# estop_receiver_rev1.net
KiCad netlist of a schematic drawn in EasyEDA Pro
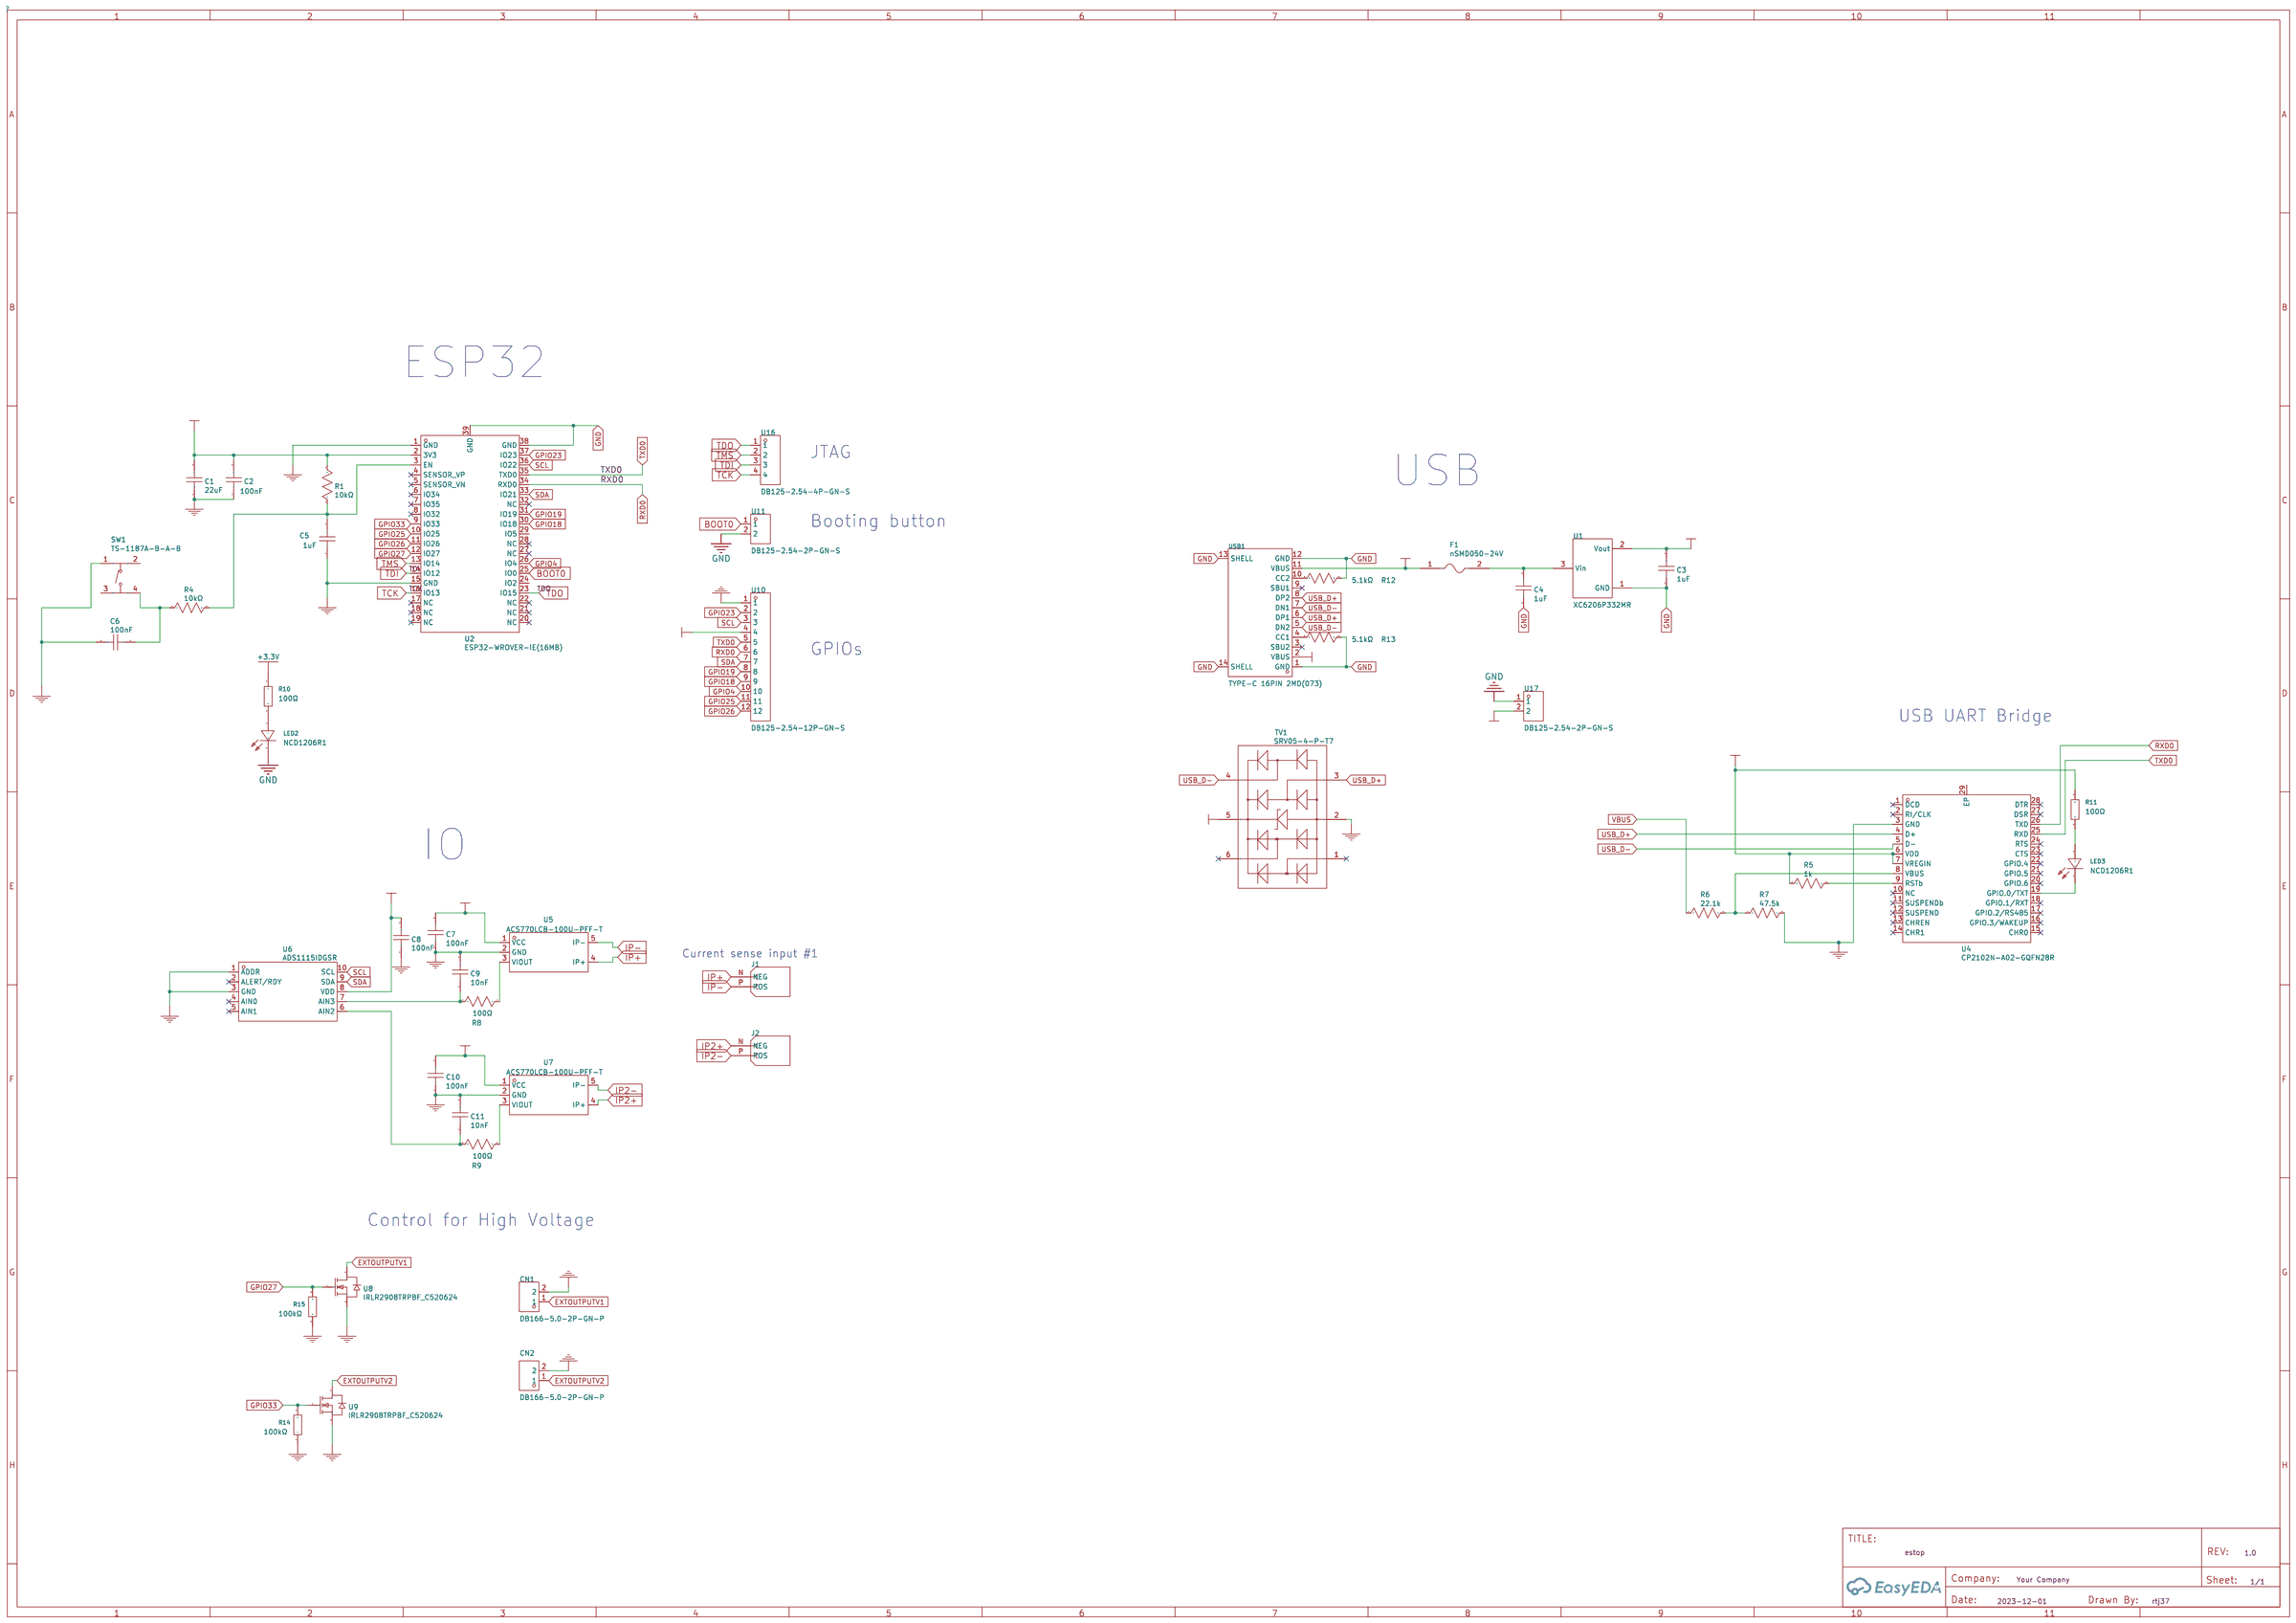
[diagram p0: schematic sheet]

(export (version "E")
  (design (tool "Eeschema 10.0.6"))
  (components
    (comp (ref "C1")
      (value "22uF")
      (fields
        (field (name "Manufacturer Part") "CL31A226KAHNNNE")
        (field (name "Manufacturer") "SAMSUNG(三星)")
      )
      (libsource (lib "easyedapro") (part "22u"))
    )
    (comp (ref "C2")
      (value "100nF")
      (fields (field (name "Manufacturer Part") "1206B104K500NT") (field (name "Manufacturer") "FH(风华)"))
      (libsource (lib "easyedapro") (part "0.1u"))
    )
    (comp (ref "C3")
      (value "1uF")
      (fields (field (name "Manufacturer Part") "1206B105K500NT") (field (name "Manufacturer") "FH(风华)"))
      (libsource (lib "easyedapro") (part "1u"))
    )
    (comp (ref "C4")
      (value "1uF")
      (fields (field (name "Manufacturer Part") "1206B105K500NT") (field (name "Manufacturer") "FH(风华)"))
      (libsource (lib "easyedapro") (part "1u"))
    )
    (comp (ref "C5")
      (value "1uF")
      (fields (field (name "Manufacturer Part") "1206B105K500NT") (field (name "Manufacturer") "FH(风华)"))
      (libsource (lib "easyedapro") (part "1u"))
    )
    (comp (ref "C6")
      (value "100nF")
      (fields (field (name "Manufacturer Part") "1206B104K500NT") (field (name "Manufacturer") "FH(风华)"))
      (libsource (lib "easyedapro") (part "0.1u"))
    )
    (comp (ref "C7")
      (value "100nF")
      (fields (field (name "Manufacturer Part") "1206B104K500NT") (field (name "Manufacturer") "FH(风华)"))
      (libsource (lib "easyedapro") (part "0.1u"))
    )
    (comp (ref "C8")
      (value "100nF")
      (fields (field (name "Manufacturer Part") "1206B104K500NT") (field (name "Manufacturer") "FH(风华)"))
      (libsource (lib "easyedapro") (part "100n"))
    )
    (comp (ref "C9")
      (value "10nF")
      (fields (field (name "Manufacturer Part") "1206B103K102CT") (field (name "Manufacturer") "Walsin(华新科)"))
      (libsource (lib "easyedapro") (part "10n"))
    )
    (comp (ref "C10")
      (value "100nF")
      (fields (field (name "Manufacturer Part") "1206B104K500NT") (field (name "Manufacturer") "FH(风华)"))
      (libsource (lib "easyedapro") (part "0.1u"))
    )
    (comp (ref "C11")
      (value "10nF")
      (fields (field (name "Manufacturer Part") "1206B103K102CT") (field (name "Manufacturer") "Walsin(华新科)"))
      (libsource (lib "easyedapro") (part "10n"))
    )
    (comp (ref "CN1")
      (value "DB166-5.0-2P-GN-P")
      (footprint "easyedapro:CONN-TH_2P-P5.00_DB166-5.0-2P-GN-P")
      (description "Pitch:5mm Number of Pins:2P")
      (fields (field (name "Manufacturer") "DORABO(地博电气)"))
      (libsource (lib "easyedapro") (part "DB166-5.0-2P-GN-P"))
    )
    (comp (ref "CN2")
      (value "DB166-5.0-2P-GN-P")
      (footprint "easyedapro:CONN-TH_2P-P5.00_DB166-5.0-2P-GN-P")
      (description "Pitch:5mm Number of Pins:2P")
      (fields (field (name "Manufacturer") "DORABO(地博电气)"))
      (libsource (lib "easyedapro") (part "DB166-5.0-2P-GN-P"))
    )
    (comp (ref "F1")
      (value "nSMD050-24V")
      (footprint "easyedapro:F1206")
      (fields (field (name "Manufacturer") "台湾陆海"))
      (libsource (lib "easyedapro") (part "nSMD050-24V"))
    )
    (comp (ref "J1")
      (value "XT90PW-F")
      (footprint "easyedapro:AMASS_XT90PW-F")
      (description "\\nSocket, DC supply, XT90, female, PIN:2, on PCBs, THT\\n")
      (libsource (lib "easyedapro") (part "XT90PW-F"))
    )
    (comp (ref "J2")
      (value "XT90PW-F")
      (footprint "easyedapro:AMASS_XT90PW-F")
      (description "\\nSocket, DC supply, XT90, female, PIN:2, on PCBs, THT\\n")
      (libsource (lib "easyedapro") (part "XT90PW-F"))
    )
    (comp (ref "LED2")
      (value "NCD1206R1")
      (footprint "easyedapro:LED1206-R-RD_RED")
      (fields (field (name "Manufacturer") "国星光电"))
      (libsource (lib "easyedapro") (part "FC-3215HRK-620D"))
    )
    (comp (ref "LED3")
      (value "NCD1206R1")
      (footprint "easyedapro:LED1206-R-RD_RED")
      (fields (field (name "Manufacturer") "国星光电"))
      (libsource (lib "easyedapro") (part "FC-3215HRK-620D"))
    )
    (comp (ref "R1")
      (value "10kΩ")
      (fields
        (field (name "Manufacturer Part") "1206W4F1002T5E")
        (field (name "Manufacturer") "UNI-ROYAL(厚声)")
      )
      (libsource (lib "easyedapro") (part "10k"))
    )
    (comp (ref "R4")
      (value "10kΩ")
      (fields
        (field (name "Manufacturer Part") "1206W4F1002T5E")
        (field (name "Manufacturer") "UNI-ROYAL(厚声)")
      )
      (libsource (lib "easyedapro") (part "0"))
    )
    (comp (ref "R5") (value "1k") (footprint "easyedapro:R1206") (libsource (lib "easyedapro") (part "1k")))
    (comp (ref "R6")
      (value "22.1k")
      (footprint "easyedapro:R1206")
      (libsource (lib "easyedapro") (part "22.1k"))
    )
    (comp (ref "R7")
      (value "47.5k")
      (footprint "easyedapro:R1206")
      (libsource (lib "easyedapro") (part "47.5k"))
    )
    (comp (ref "R8")
      (value "100Ω")
      (fields
        (field (name "Manufacturer Part") "1206W4F1000T5E")
        (field (name "Manufacturer") "UNI-ROYAL(厚声)")
      )
      (libsource (lib "easyedapro") (part "100"))
    )
    (comp (ref "R9")
      (value "100Ω")
      (fields
        (field (name "Manufacturer Part") "1206W4F1000T5E")
        (field (name "Manufacturer") "UNI-ROYAL(厚声)")
      )
      (libsource (lib "easyedapro") (part "100"))
    )
    (comp (ref "R10")
      (value "100Ω")
      (footprint "easyedapro:R1206")
      (fields
        (field (name "Manufacturer Part") "1206W4F1000T5E")
        (field (name "Manufacturer") "UNI-ROYAL(厚声)")
      )
      (libsource (lib "easyedapro") (part "1206W4F1000T5E"))
    )
    (comp (ref "R11")
      (value "100Ω")
      (footprint "easyedapro:R1206")
      (fields
        (field (name "Manufacturer Part") "1206W4F1000T5E")
        (field (name "Manufacturer") "UNI-ROYAL(厚声)")
      )
      (libsource (lib "easyedapro") (part "1206W4F1000T5E"))
    )
    (comp (ref "R12")
      (value "5.1kΩ")
      (fields
        (field (name "Manufacturer Part") "1206W4F5101T5E")
        (field (name "Manufacturer") "UNI-ROYAL(厚声)")
      )
      (libsource (lib "easyedapro") (part "5.1k"))
    )
    (comp (ref "R13")
      (value "5.1kΩ")
      (fields
        (field (name "Manufacturer Part") "1206W4F5101T5E")
        (field (name "Manufacturer") "UNI-ROYAL(厚声)")
      )
      (libsource (lib "easyedapro") (part "5.1k"))
    )
    (comp (ref "R14")
      (value "100kΩ")
      (footprint "easyedapro:R1206")
      (fields
        (field (name "Manufacturer Part") "1206W4F1003T5E")
        (field (name "Manufacturer") "UNI-ROYAL(厚声)")
      )
      (libsource (lib "easyedapro") (part "1206W4F1003T5E"))
    )
    (comp (ref "R15")
      (value "100kΩ")
      (footprint "easyedapro:R1206")
      (fields
        (field (name "Manufacturer Part") "1206W4F1003T5E")
        (field (name "Manufacturer") "UNI-ROYAL(厚声)")
      )
      (libsource (lib "easyedapro") (part "1206W4F1003T5E"))
    )
    (comp (ref "SW1")
      (value "TS-1187A-B-A-B")
      (footprint "easyedapro:SW-SMD_4P-L5.1-W5.1-P3.70-LS6.5-TL-2")
      (fields (field (name "Manufacturer") "XKB Connectivity(中国星坤)"))
      (libsource (lib "easyedapro") (part "TS-1187A-B-A-B"))
    )
    (comp (ref "TV1")
      (value "SRV05-4-P-T7")
      (footprint "easyedapro:SOT-23-6_L2.9-W1.6-P0.95-LS2.8-BR")
      (fields (field (name "Manufacturer") "PROTEK"))
      (libsource (lib "easyedapro") (part "SRV05-4-P-T7"))
    )
    (comp (ref "U1")
      (value "XC6206P332MR")
      (footprint "easyedapro:SOT-23-3_L2.9-W1.6-P1.90-LS2.8-BR")
      (fields (field (name "Manufacturer") "TOREX(特瑞仕)"))
      (libsource (lib "easyedapro") (part "XC6206P332MR"))
    )
    (comp (ref "U2")
      (value "ESP32-WROVER-IE(16MB)")
      (footprint "easyedapro:WIFI-SMD_ESP32-WROVER-E")
      (fields
        (field (name "Manufacturer Part") "ESP32-WROVER-IE-N16R8")
        (field (name "Manufacturer") "ESPRESSIF(乐鑫)")
      )
      (libsource (lib "easyedapro") (part "ESP32-WROVER-IE(16MB)"))
    )
    (comp (ref "U4")
      (value "CP2102N-A02-GQFN28R")
      (footprint "easyedapro:QFN-28_L5.0-W5.0-P0.50-TL-EP3.3")
      (fields (field (name "Manufacturer") "SILICON LABS(芯科)"))
      (libsource (lib "easyedapro") (part "CP2102N-A02-GQFN28R"))
    )
    (comp (ref "U5")
      (value "ACS770LCB-100U-PFF-T")
      (footprint "easyedapro:SENSOR-TH_ACS770LCB-100U-PFF-T")
      (fields (field (name "Manufacturer") "ALLEGRO(美国埃戈罗)"))
      (libsource (lib "easyedapro") (part "ACS770LCB-100U-PFF-T"))
    )
    (comp (ref "U6")
      (value "ADS1115IDGSR")
      (footprint "easyedapro:MSOP-10_L3.0-W3.0-P0.50-LS5.0-BL")
      (fields (field (name "Manufacturer") "TI(德州仪器)"))
      (libsource (lib "easyedapro") (part "ADS1115IDGSR"))
    )
    (comp (ref "U7")
      (value "ACS770LCB-100U-PFF-T")
      (footprint "easyedapro:SENSOR-TH_ACS770LCB-100U-PFF-T")
      (fields (field (name "Manufacturer") "ALLEGRO(美国埃戈罗)"))
      (libsource (lib "easyedapro") (part "ACS770LCB-100U-PFF-T"))
    )
    (comp (ref "U8")
      (value "IRLR2908TRPBF_C520624")
      (footprint "easyedapro:TO-252-3_L6.5-W6.1-P4.58-LS9.9-BR")
      (fields
        (field (name "Manufacturer Part") "IRLR2908TRPBF")
        (field (name "Manufacturer") "Infineon(英飞凌)")
      )
      (libsource (lib "easyedapro") (part "IRLR2908TRPBF_C520624"))
    )
    (comp (ref "U9")
      (value "IRLR2908TRPBF_C520624")
      (footprint "easyedapro:TO-252-3_L6.5-W6.1-P4.58-LS9.9-BR")
      (fields
        (field (name "Manufacturer Part") "IRLR2908TRPBF")
        (field (name "Manufacturer") "Infineon(英飞凌)")
      )
      (libsource (lib "easyedapro") (part "IRLR2908TRPBF_C520624"))
    )
    (comp (ref "U10")
      (value "DB125-2.54-12P-GN-S")
      (footprint "easyedapro:CONN-TH_DB125-2.54-12P-GN")
      (fields (field (name "Manufacturer") "DORABO(地博电气)"))
      (libsource (lib "easyedapro") (part "DB125-2.54-12P-GN"))
    )
    (comp (ref "U11")
      (value "DB125-2.54-2P-GN-S")
      (footprint "easyedapro:CONN-TH_DB125-2.54-2P-GN")
      (fields (field (name "Manufacturer") "DORABO(地博电气)"))
      (libsource (lib "easyedapro") (part "DB125-2.54-2P-GN"))
    )
    (comp (ref "U16")
      (value "DB125-2.54-4P-GN-S")
      (footprint "easyedapro:CONN-TH_DB125-2.54-4P-GN")
      (fields (field (name "Manufacturer") "DORABO(地博电气)"))
      (libsource (lib "easyedapro") (part "DB125-2.54-4P-GN"))
    )
    (comp (ref "U17")
      (value "DB125-2.54-2P-GN-S")
      (footprint "easyedapro:CONN-TH_DB125-2.54-2P-GN")
      (fields (field (name "Manufacturer") "DORABO(地博电气)"))
      (libsource (lib "easyedapro") (part "DB125-2.54-2P-GN"))
    )
    (comp (ref "USB1")
      (value "TYPE-C 16PIN 2MD(073)")
      (footprint "easyedapro:USB-C-SMD_TYPE-C-6PIN-2MD-073")
      (fields (field (name "Manufacturer") "SHOU HAN(首韩)"))
      (libsource (lib "easyedapro") (part "TYPE-C 16PIN 2MD(073)"))
    )
  )
  (nets
    (net (code "1") (name "+3.3V") (class "Default")
      (node (ref "C1") (pin "2") (pinfunction "2_2") (pintype "unspecified"))
      (node (ref "C2") (pin "2") (pinfunction "2_2") (pintype "unspecified"))
      (node (ref "C3") (pin "2") (pinfunction "2_2") (pintype "unspecified"))
      (node (ref "C8") (pin "2") (pinfunction "2_2") (pintype "unspecified"))
      (node (ref "R1") (pin "2") (pinfunction "2_2") (pintype "unspecified"))
      (node (ref "R10") (pin "1") (pinfunction "1_1") (pintype "input"))
      (node (ref "R11") (pin "1") (pinfunction "1_1") (pintype "input"))
      (node (ref "R5") (pin "1") (pinfunction "1_1") (pintype "unspecified"))
      (node (ref "U1") (pin "2") (pinfunction "Vout_2") (pintype "unspecified"))
      (node (ref "U10") (pin "4") (pinfunction "4_4") (pintype "unspecified"))
      (node (ref "U2") (pin "2") (pinfunction "3V3_2") (pintype "unspecified"))
      (node (ref "U4") (pin "6") (pinfunction "VDD_6") (pintype "unspecified"))
      (node (ref "U4") (pin "7") (pinfunction "VREGIN_7") (pintype "unspecified"))
      (node (ref "U6") (pin "8") (pinfunction "VDD_8") (pintype "unspecified"))
    )
    (net (code "2") (name "BOOT0") (class "Default")
      (node (ref "U11") (pin "1") (pinfunction "1_1") (pintype "unspecified"))
      (node (ref "U2") (pin "25") (pinfunction "IO0_25") (pintype "unspecified"))
    )
    (net (code "3") (name "EXTOUTPUTV1") (class "Default")
      (node (ref "CN1") (pin "1") (pinfunction "1_1") (pintype "unspecified"))
      (node (ref "U8") (pin "2") (pinfunction "D_2") (pintype "unspecified"))
    )
    (net (code "4") (name "EXTOUTPUTV2") (class "Default")
      (node (ref "CN2") (pin "1") (pinfunction "1_1") (pintype "unspecified"))
      (node (ref "U9") (pin "2") (pinfunction "D_2") (pintype "unspecified"))
    )
    (net (code "5") (name "GND") (class "Default")
      (node (ref "C1") (pin "1") (pinfunction "1_1") (pintype "unspecified"))
      (node (ref "C10") (pin "1") (pinfunction "1_1") (pintype "unspecified"))
      (node (ref "C11") (pin "2") (pinfunction "2_2") (pintype "unspecified"))
      (node (ref "C2") (pin "1") (pinfunction "1_1") (pintype "unspecified"))
      (node (ref "C3") (pin "1") (pinfunction "1_1") (pintype "unspecified"))
      (node (ref "C4") (pin "1") (pinfunction "1_1") (pintype "unspecified"))
      (node (ref "C5") (pin "1") (pinfunction "1_1") (pintype "unspecified"))
      (node (ref "C6") (pin "1") (pinfunction "1_1") (pintype "unspecified"))
      (node (ref "C7") (pin "1") (pinfunction "1_1") (pintype "unspecified"))
      (node (ref "C8") (pin "1") (pinfunction "1_1") (pintype "unspecified"))
      (node (ref "C9") (pin "2") (pinfunction "2_2") (pintype "unspecified"))
      (node (ref "CN1") (pin "2") (pinfunction "2_2") (pintype "unspecified"))
      (node (ref "CN2") (pin "2") (pinfunction "2_2") (pintype "unspecified"))
      (node (ref "LED2") (pin "2") (pinfunction "K_2") (pintype "input"))
      (node (ref "R12") (pin "2") (pinfunction "2_2") (pintype "unspecified"))
      (node (ref "R13") (pin "2") (pinfunction "2_2") (pintype "unspecified"))
      (node (ref "R14") (pin "1") (pinfunction "1_1") (pintype "input"))
      (node (ref "R15") (pin "1") (pinfunction "1_1") (pintype "input"))
      (node (ref "R7") (pin "2") (pinfunction "2_2") (pintype "unspecified"))
      (node (ref "SW1") (pin "1") (pinfunction "A_1") (pintype "unspecified"))
      (node (ref "TV1") (pin "2") (pinfunction "2_2") (pintype "input"))
      (node (ref "U1") (pin "1") (pinfunction "GND_1") (pintype "unspecified"))
      (node (ref "U10") (pin "1") (pinfunction "1_1") (pintype "unspecified"))
      (node (ref "U11") (pin "2") (pinfunction "2_2") (pintype "unspecified"))
      (node (ref "U17") (pin "1") (pinfunction "1_1") (pintype "unspecified"))
      (node (ref "U2") (pin "1") (pinfunction "GND_1") (pintype "unspecified"))
      (node (ref "U2") (pin "15") (pinfunction "GND_15") (pintype "unspecified"))
      (node (ref "U2") (pin "38") (pinfunction "GND_38") (pintype "unspecified"))
      (node (ref "U2") (pin "39") (pinfunction "GND_39") (pintype "unspecified"))
      (node (ref "U4") (pin "3") (pinfunction "GND_3") (pintype "unspecified"))
      (node (ref "U5") (pin "2") (pinfunction "GND_2") (pintype "unspecified"))
      (node (ref "U6") (pin "1") (pinfunction "ADDR_1") (pintype "unspecified"))
      (node (ref "U6") (pin "3") (pinfunction "GND_3") (pintype "unspecified"))
      (node (ref "U7") (pin "2") (pinfunction "GND_2") (pintype "unspecified"))
      (node (ref "U8") (pin "3") (pinfunction "S_3") (pintype "unspecified"))
      (node (ref "U9") (pin "3") (pinfunction "S_3") (pintype "unspecified"))
      (node (ref "USB1") (pin "1") (pinfunction "GND_1") (pintype "input"))
      (node (ref "USB1") (pin "12") (pinfunction "GND_12") (pintype "input"))
      (node (ref "USB1") (pin "13") (pinfunction "SHELL_13") (pintype "input"))
      (node (ref "USB1") (pin "14") (pinfunction "SHELL_14") (pintype "input"))
    )
    (net (code "6") (name "GPIO4") (class "Default")
      (node (ref "U10") (pin "10") (pinfunction "10_10") (pintype "unspecified"))
      (node (ref "U2") (pin "26") (pinfunction "IO4_26") (pintype "unspecified"))
    )
    (net (code "7") (name "GPIO18") (class "Default")
      (node (ref "U10") (pin "9") (pinfunction "9_9") (pintype "unspecified"))
      (node (ref "U2") (pin "30") (pinfunction "IO18_30") (pintype "unspecified"))
    )
    (net (code "8") (name "GPIO19") (class "Default")
      (node (ref "U10") (pin "8") (pinfunction "8_8") (pintype "unspecified"))
      (node (ref "U2") (pin "31") (pinfunction "IO19_31") (pintype "unspecified"))
    )
    (net (code "9") (name "GPIO23") (class "Default")
      (node (ref "U10") (pin "2") (pinfunction "2_2") (pintype "unspecified"))
      (node (ref "U2") (pin "37") (pinfunction "IO23_37") (pintype "unspecified"))
    )
    (net (code "10") (name "GPIO25") (class "Default")
      (node (ref "U10") (pin "11") (pinfunction "11_11") (pintype "unspecified"))
      (node (ref "U2") (pin "10") (pinfunction "IO25_10") (pintype "unspecified"))
    )
    (net (code "11") (name "GPIO26") (class "Default")
      (node (ref "U10") (pin "12") (pinfunction "12_12") (pintype "unspecified"))
      (node (ref "U2") (pin "11") (pinfunction "IO26_11") (pintype "unspecified"))
    )
    (net (code "12") (name "GPIO27") (class "Default")
      (node (ref "R15") (pin "2") (pinfunction "2_2") (pintype "input"))
      (node (ref "U2") (pin "12") (pinfunction "IO27_12") (pintype "unspecified"))
      (node (ref "U8") (pin "1") (pinfunction "G_1") (pintype "unspecified"))
    )
    (net (code "13") (name "GPIO33") (class "Default")
      (node (ref "R14") (pin "2") (pinfunction "2_2") (pintype "input"))
      (node (ref "U2") (pin "9") (pinfunction "IO33_9") (pintype "unspecified"))
      (node (ref "U9") (pin "1") (pinfunction "G_1") (pintype "unspecified"))
    )
    (net (code "14") (name "IP+") (class "Default")
      (node (ref "J1") (pin "N") (pinfunction "NEG_N") (pintype "unspecified"))
      (node (ref "U5") (pin "4") (pinfunction "IP+_4") (pintype "unspecified"))
    )
    (net (code "15") (name "IP-") (class "Default")
      (node (ref "J1") (pin "P") (pinfunction "POS_P") (pintype "unspecified"))
      (node (ref "U5") (pin "5") (pinfunction "IP-_5") (pintype "unspecified"))
    )
    (net (code "16") (name "IP2+") (class "Default")
      (node (ref "J2") (pin "N") (pinfunction "NEG_N") (pintype "unspecified"))
      (node (ref "U7") (pin "4") (pinfunction "IP+_4") (pintype "unspecified"))
    )
    (net (code "17") (name "IP2-") (class "Default")
      (node (ref "J2") (pin "P") (pinfunction "POS_P") (pintype "unspecified"))
      (node (ref "U7") (pin "5") (pinfunction "IP-_5") (pintype "unspecified"))
    )
    (net (code "18") (name "Net-(LED2-A)") (class "Default")
      (node (ref "LED2") (pin "1") (pinfunction "A_1") (pintype "input"))
      (node (ref "R10") (pin "2") (pinfunction "2_2") (pintype "input"))
    )
    (net (code "19") (name "Net-(LED3-A)") (class "Default")
      (node (ref "LED3") (pin "1") (pinfunction "A_1") (pintype "input"))
      (node (ref "R11") (pin "2") (pinfunction "2_2") (pintype "input"))
    )
    (net (code "20") (name "Net-(LED3-K)") (class "Default")
      (node (ref "LED3") (pin "2") (pinfunction "K_2") (pintype "input"))
      (node (ref "U4") (pin "19") (pinfunction "GPIO.0/TXT_19") (pintype "unspecified"))
    )
    (net (code "21") (name "Net-(SW1-D)") (class "Default")
      (node (ref "C6") (pin "2") (pinfunction "2_2") (pintype "unspecified"))
      (node (ref "R4") (pin "1") (pinfunction "1_1") (pintype "unspecified"))
      (node (ref "SW1") (pin "4") (pinfunction "D_4") (pintype "unspecified"))
    )
    (net (code "22") (name "Net-(U1-Vin)") (class "Default")
      (node (ref "C4") (pin "2") (pinfunction "2_2") (pintype "unspecified"))
      (node (ref "F1") (pin "2") (pinfunction "2_2") (pintype "unspecified"))
      (node (ref "U1") (pin "3") (pinfunction "Vin_3") (pintype "unspecified"))
    )
    (net (code "23") (name "Net-(U2-EN)") (class "Default")
      (node (ref "C5") (pin "2") (pinfunction "2_2") (pintype "unspecified"))
      (node (ref "R1") (pin "1") (pinfunction "1_1") (pintype "unspecified"))
      (node (ref "R4") (pin "2") (pinfunction "2_2") (pintype "unspecified"))
      (node (ref "U2") (pin "3") (pinfunction "EN_3") (pintype "unspecified"))
    )
    (net (code "24") (name "Net-(U4-RSTb)") (class "Default")
      (node (ref "R5") (pin "2") (pinfunction "2_2") (pintype "unspecified"))
      (node (ref "U4") (pin "9") (pinfunction "RSTb_9") (pintype "unspecified"))
    )
    (net (code "25") (name "Net-(U4-VBUS)") (class "Default")
      (node (ref "R6") (pin "2") (pinfunction "2_2") (pintype "unspecified"))
      (node (ref "R7") (pin "1") (pinfunction "1_1") (pintype "unspecified"))
      (node (ref "U4") (pin "8") (pinfunction "VBUS_8") (pintype "unspecified"))
    )
    (net (code "26") (name "Net-(U5-VIOUT)") (class "Default")
      (node (ref "R8") (pin "1") (pinfunction "1_1") (pintype "unspecified"))
      (node (ref "U5") (pin "3") (pinfunction "VIOUT_3") (pintype "unspecified"))
    )
    (net (code "27") (name "Net-(U6-AIN2)") (class "Default")
      (node (ref "C11") (pin "1") (pinfunction "1_1") (pintype "unspecified"))
      (node (ref "R9") (pin "2") (pinfunction "2_2") (pintype "unspecified"))
      (node (ref "U6") (pin "6") (pinfunction "AIN2_6") (pintype "unspecified"))
    )
    (net (code "28") (name "Net-(U6-AIN3)") (class "Default")
      (node (ref "C9") (pin "1") (pinfunction "1_1") (pintype "unspecified"))
      (node (ref "R8") (pin "2") (pinfunction "2_2") (pintype "unspecified"))
      (node (ref "U6") (pin "7") (pinfunction "AIN3_7") (pintype "unspecified"))
    )
    (net (code "29") (name "Net-(U7-VIOUT)") (class "Default")
      (node (ref "R9") (pin "1") (pinfunction "1_1") (pintype "unspecified"))
      (node (ref "U7") (pin "3") (pinfunction "VIOUT_3") (pintype "unspecified"))
    )
    (net (code "30") (name "Net-(USB1-CC1)") (class "Default")
      (node (ref "R13") (pin "1") (pinfunction "1_1") (pintype "unspecified"))
      (node (ref "USB1") (pin "4") (pinfunction "CC1_4") (pintype "input"))
    )
    (net (code "31") (name "Net-(USB1-CC2)") (class "Default")
      (node (ref "R12") (pin "1") (pinfunction "1_1") (pintype "unspecified"))
      (node (ref "USB1") (pin "10") (pinfunction "CC2_10") (pintype "input"))
    )
    (net (code "32") (name "RXD0") (class "Default")
      (node (ref "U10") (pin "6") (pinfunction "6_6") (pintype "unspecified"))
      (node (ref "U2") (pin "34") (pinfunction "RXD0_34") (pintype "unspecified"))
      (node (ref "U4") (pin "26") (pinfunction "TXD_26") (pintype "unspecified"))
    )
    (net (code "33") (name "SCL") (class "Default")
      (node (ref "U10") (pin "3") (pinfunction "3_3") (pintype "unspecified"))
      (node (ref "U2") (pin "36") (pinfunction "IO22_36") (pintype "unspecified"))
      (node (ref "U6") (pin "10") (pinfunction "SCL_10") (pintype "unspecified"))
    )
    (net (code "34") (name "SDA") (class "Default")
      (node (ref "U10") (pin "7") (pinfunction "7_7") (pintype "unspecified"))
      (node (ref "U2") (pin "33") (pinfunction "IO21_33") (pintype "unspecified"))
      (node (ref "U6") (pin "9") (pinfunction "SDA_9") (pintype "unspecified"))
    )
    (net (code "35") (name "TCK") (class "Default")
      (node (ref "U16") (pin "4") (pinfunction "4_4") (pintype "unspecified"))
      (node (ref "U2") (pin "16") (pinfunction "IO13_16") (pintype "unspecified"))
    )
    (net (code "36") (name "TDI") (class "Default")
      (node (ref "U16") (pin "3") (pinfunction "3_3") (pintype "unspecified"))
      (node (ref "U2") (pin "14") (pinfunction "IO12_14") (pintype "unspecified"))
    )
    (net (code "37") (name "TDO") (class "Default")
      (node (ref "U16") (pin "1") (pinfunction "1_1") (pintype "unspecified"))
      (node (ref "U2") (pin "23") (pinfunction "IO15_23") (pintype "unspecified"))
    )
    (net (code "38") (name "TMS") (class "Default")
      (node (ref "U16") (pin "2") (pinfunction "2_2") (pintype "unspecified"))
      (node (ref "U2") (pin "13") (pinfunction "IO14_13") (pintype "unspecified"))
    )
    (net (code "39") (name "TXD0") (class "Default")
      (node (ref "U10") (pin "5") (pinfunction "5_5") (pintype "unspecified"))
      (node (ref "U2") (pin "35") (pinfunction "TXD0_35") (pintype "unspecified"))
      (node (ref "U4") (pin "25") (pinfunction "RXD_25") (pintype "unspecified"))
    )
    (net (code "40") (name "USB_D+") (class "Default")
      (node (ref "TV1") (pin "3") (pinfunction "3_3") (pintype "input"))
      (node (ref "U4") (pin "4") (pinfunction "D+_4") (pintype "unspecified"))
      (node (ref "USB1") (pin "6") (pinfunction "DP1_6") (pintype "input"))
      (node (ref "USB1") (pin "8") (pinfunction "DP2_8") (pintype "input"))
    )
    (net (code "41") (name "USB_D-") (class "Default")
      (node (ref "TV1") (pin "4") (pinfunction "4_4") (pintype "input"))
      (node (ref "U4") (pin "5") (pinfunction "D-_5") (pintype "unspecified"))
      (node (ref "USB1") (pin "5") (pinfunction "DN2_5") (pintype "input"))
      (node (ref "USB1") (pin "7") (pinfunction "DN1_7") (pintype "input"))
    )
    (net (code "42") (name "VBUS") (class "Default")
      (node (ref "C10") (pin "2") (pinfunction "2_2") (pintype "unspecified"))
      (node (ref "C7") (pin "2") (pinfunction "2_2") (pintype "unspecified"))
      (node (ref "F1") (pin "1") (pinfunction "1_1") (pintype "unspecified"))
      (node (ref "R6") (pin "1") (pinfunction "1_1") (pintype "unspecified"))
      (node (ref "TV1") (pin "5") (pinfunction "5_5") (pintype "input"))
      (node (ref "U17") (pin "2") (pinfunction "2_2") (pintype "unspecified"))
      (node (ref "U5") (pin "1") (pinfunction "VCC_1") (pintype "unspecified"))
      (node (ref "U7") (pin "1") (pinfunction "VCC_1") (pintype "unspecified"))
      (node (ref "USB1") (pin "11") (pinfunction "VBUS_11") (pintype "input"))
      (node (ref "USB1") (pin "2") (pinfunction "VBUS_2") (pintype "input"))
    )
    (net (code "43") (name "unconnected-(SW1-B-Pad2)") (class "Default")
      (node (ref "SW1") (pin "2") (pinfunction "B_2") (pintype "unspecified"))
    )
    (net (code "44") (name "unconnected-(SW1-C-Pad3)") (class "Default")
      (node (ref "SW1") (pin "3") (pinfunction "C_3") (pintype "unspecified"))
    )
    (net (code "45") (name "unconnected-(TV1-Pad1)") (class "Default")
      (node (ref "TV1") (pin "1") (pinfunction "1_1") (pintype "input+no_connect"))
    )
    (net (code "46") (name "unconnected-(TV1-Pad6)") (class "Default")
      (node (ref "TV1") (pin "6") (pinfunction "6_6") (pintype "input+no_connect"))
    )
    (net (code "47") (name "unconnected-(U2-IO2-Pad24)") (class "Default")
      (node (ref "U2") (pin "24") (pinfunction "IO2_24") (pintype "unspecified"))
    )
    (net (code "48") (name "unconnected-(U2-IO5-Pad29)") (class "Default")
      (node (ref "U2") (pin "29") (pinfunction "IO5_29") (pintype "unspecified"))
    )
    (net (code "49") (name "unconnected-(U2-IO32-Pad8)") (class "Default")
      (node (ref "U2") (pin "8") (pinfunction "IO32_8") (pintype "unspecified+no_connect"))
    )
    (net (code "50") (name "unconnected-(U2-IO34-Pad6)") (class "Default")
      (node (ref "U2") (pin "6") (pinfunction "IO34_6") (pintype "unspecified+no_connect"))
    )
    (net (code "51") (name "unconnected-(U2-IO35-Pad7)") (class "Default")
      (node (ref "U2") (pin "7") (pinfunction "IO35_7") (pintype "unspecified+no_connect"))
    )
    (net (code "52") (name "unconnected-(U2-NC-Pad17)") (class "Default")
      (node (ref "U2") (pin "17") (pinfunction "NC_17") (pintype "unspecified+no_connect"))
    )
    (net (code "53") (name "unconnected-(U2-NC-Pad18)") (class "Default")
      (node (ref "U2") (pin "18") (pinfunction "NC_18") (pintype "unspecified+no_connect"))
    )
    (net (code "54") (name "unconnected-(U2-NC-Pad19)") (class "Default")
      (node (ref "U2") (pin "19") (pinfunction "NC_19") (pintype "unspecified+no_connect"))
    )
    (net (code "55") (name "unconnected-(U2-NC-Pad20)") (class "Default")
      (node (ref "U2") (pin "20") (pinfunction "NC_20") (pintype "unspecified+no_connect"))
    )
    (net (code "56") (name "unconnected-(U2-NC-Pad21)") (class "Default")
      (node (ref "U2") (pin "21") (pinfunction "NC_21") (pintype "unspecified+no_connect"))
    )
    (net (code "57") (name "unconnected-(U2-NC-Pad22)") (class "Default")
      (node (ref "U2") (pin "22") (pinfunction "NC_22") (pintype "unspecified+no_connect"))
    )
    (net (code "58") (name "unconnected-(U2-NC-Pad27)") (class "Default")
      (node (ref "U2") (pin "27") (pinfunction "NC_27") (pintype "unspecified+no_connect"))
    )
    (net (code "59") (name "unconnected-(U2-NC-Pad28)") (class "Default")
      (node (ref "U2") (pin "28") (pinfunction "NC_28") (pintype "unspecified+no_connect"))
    )
    (net (code "60") (name "unconnected-(U2-NC-Pad32)") (class "Default")
      (node (ref "U2") (pin "32") (pinfunction "NC_32") (pintype "unspecified+no_connect"))
    )
    (net (code "61") (name "unconnected-(U2-SENSOR_VN-Pad5)") (class "Default")
      (node (ref "U2") (pin "5") (pinfunction "SENSOR_VN_5") (pintype "unspecified+no_connect"))
    )
    (net (code "62") (name "unconnected-(U2-SENSOR_VP-Pad4)") (class "Default")
      (node (ref "U2") (pin "4") (pinfunction "SENSOR_VP_4") (pintype "unspecified+no_connect"))
    )
    (net (code "63") (name "unconnected-(U4-CHR0-Pad15)") (class "Default")
      (node (ref "U4") (pin "15") (pinfunction "CHR0_15") (pintype "unspecified+no_connect"))
    )
    (net (code "64") (name "unconnected-(U4-CHR1-Pad14)") (class "Default")
      (node (ref "U4") (pin "14") (pinfunction "CHR1_14") (pintype "unspecified+no_connect"))
    )
    (net (code "65") (name "unconnected-(U4-CHREN-Pad13)") (class "Default")
      (node (ref "U4") (pin "13") (pinfunction "CHREN_13") (pintype "unspecified+no_connect"))
    )
    (net (code "66") (name "unconnected-(U4-CTS-Pad23)") (class "Default")
      (node (ref "U4") (pin "23") (pinfunction "CTS_23") (pintype "unspecified+no_connect"))
    )
    (net (code "67") (name "unconnected-(U4-DCD-Pad1)") (class "Default")
      (node (ref "U4") (pin "1") (pinfunction "DCD_1") (pintype "unspecified+no_connect"))
    )
    (net (code "68") (name "unconnected-(U4-DSR-Pad27)") (class "Default")
      (node (ref "U4") (pin "27") (pinfunction "DSR_27") (pintype "unspecified+no_connect"))
    )
    (net (code "69") (name "unconnected-(U4-DTR-Pad28)") (class "Default")
      (node (ref "U4") (pin "28") (pinfunction "DTR_28") (pintype "unspecified+no_connect"))
    )
    (net (code "70") (name "unconnected-(U4-EP-Pad29)") (class "Default")
      (node (ref "U4") (pin "29") (pinfunction "EP_29") (pintype "unspecified"))
    )
    (net (code "71") (name "unconnected-(U4-GPIO.1{slash}RXT-Pad18)") (class "Default")
      (node (ref "U4") (pin "18") (pinfunction "GPIO.1/RXT_18") (pintype "unspecified+no_connect"))
    )
    (net (code "72") (name "unconnected-(U4-GPIO.2{slash}RS485-Pad17)") (class "Default")
      (node (ref "U4") (pin "17") (pinfunction "GPIO.2/RS485_17") (pintype "unspecified+no_connect"))
    )
    (net (code "73") (name "unconnected-(U4-GPIO.3{slash}WAKEUP-Pad16)") (class "Default")
      (node (ref "U4") (pin "16") (pinfunction "GPIO.3/WAKEUP_16") (pintype "unspecified+no_connect"))
    )
    (net (code "74") (name "unconnected-(U4-GPIO.4-Pad22)") (class "Default")
      (node (ref "U4") (pin "22") (pinfunction "GPIO.4_22") (pintype "unspecified+no_connect"))
    )
    (net (code "75") (name "unconnected-(U4-GPIO.5-Pad21)") (class "Default")
      (node (ref "U4") (pin "21") (pinfunction "GPIO.5_21") (pintype "unspecified+no_connect"))
    )
    (net (code "76") (name "unconnected-(U4-GPIO.6-Pad20)") (class "Default")
      (node (ref "U4") (pin "20") (pinfunction "GPIO.6_20") (pintype "unspecified+no_connect"))
    )
    (net (code "77") (name "unconnected-(U4-NC-Pad10)") (class "Default")
      (node (ref "U4") (pin "10") (pinfunction "NC_10") (pintype "unspecified+no_connect"))
    )
    (net (code "78") (name "unconnected-(U4-RI{slash}CLK-Pad2)") (class "Default")
      (node (ref "U4") (pin "2") (pinfunction "RI/CLK_2") (pintype "unspecified+no_connect"))
    )
    (net (code "79") (name "unconnected-(U4-RTS-Pad24)") (class "Default")
      (node (ref "U4") (pin "24") (pinfunction "RTS_24") (pintype "unspecified+no_connect"))
    )
    (net (code "80") (name "unconnected-(U4-SUSPEND-Pad12)") (class "Default")
      (node (ref "U4") (pin "12") (pinfunction "SUSPEND_12") (pintype "unspecified+no_connect"))
    )
    (net (code "81") (name "unconnected-(U4-SUSPENDb-Pad11)") (class "Default")
      (node (ref "U4") (pin "11") (pinfunction "SUSPENDb_11") (pintype "unspecified+no_connect"))
    )
    (net (code "82") (name "unconnected-(U6-AIN0-Pad4)") (class "Default")
      (node (ref "U6") (pin "4") (pinfunction "AIN0_4") (pintype "unspecified+no_connect"))
    )
    (net (code "83") (name "unconnected-(U6-AIN1-Pad5)") (class "Default")
      (node (ref "U6") (pin "5") (pinfunction "AIN1_5") (pintype "unspecified+no_connect"))
    )
    (net (code "84") (name "unconnected-(U6-ALERT{slash}RDY-Pad2)") (class "Default")
      (node (ref "U6") (pin "2") (pinfunction "ALERT/RDY_2") (pintype "unspecified+no_connect"))
    )
    (net (code "85") (name "unconnected-(USB1-SBU1-Pad9)") (class "Default")
      (node (ref "USB1") (pin "9") (pinfunction "SBU1_9") (pintype "input+no_connect"))
    )
    (net (code "86") (name "unconnected-(USB1-SBU2-Pad3)") (class "Default")
      (node (ref "USB1") (pin "3") (pinfunction "SBU2_3") (pintype "input+no_connect"))
    )
  )
)
